# Rocket32_TRASIO.net
KiCad netlist of a schematic drawn in EAGLE
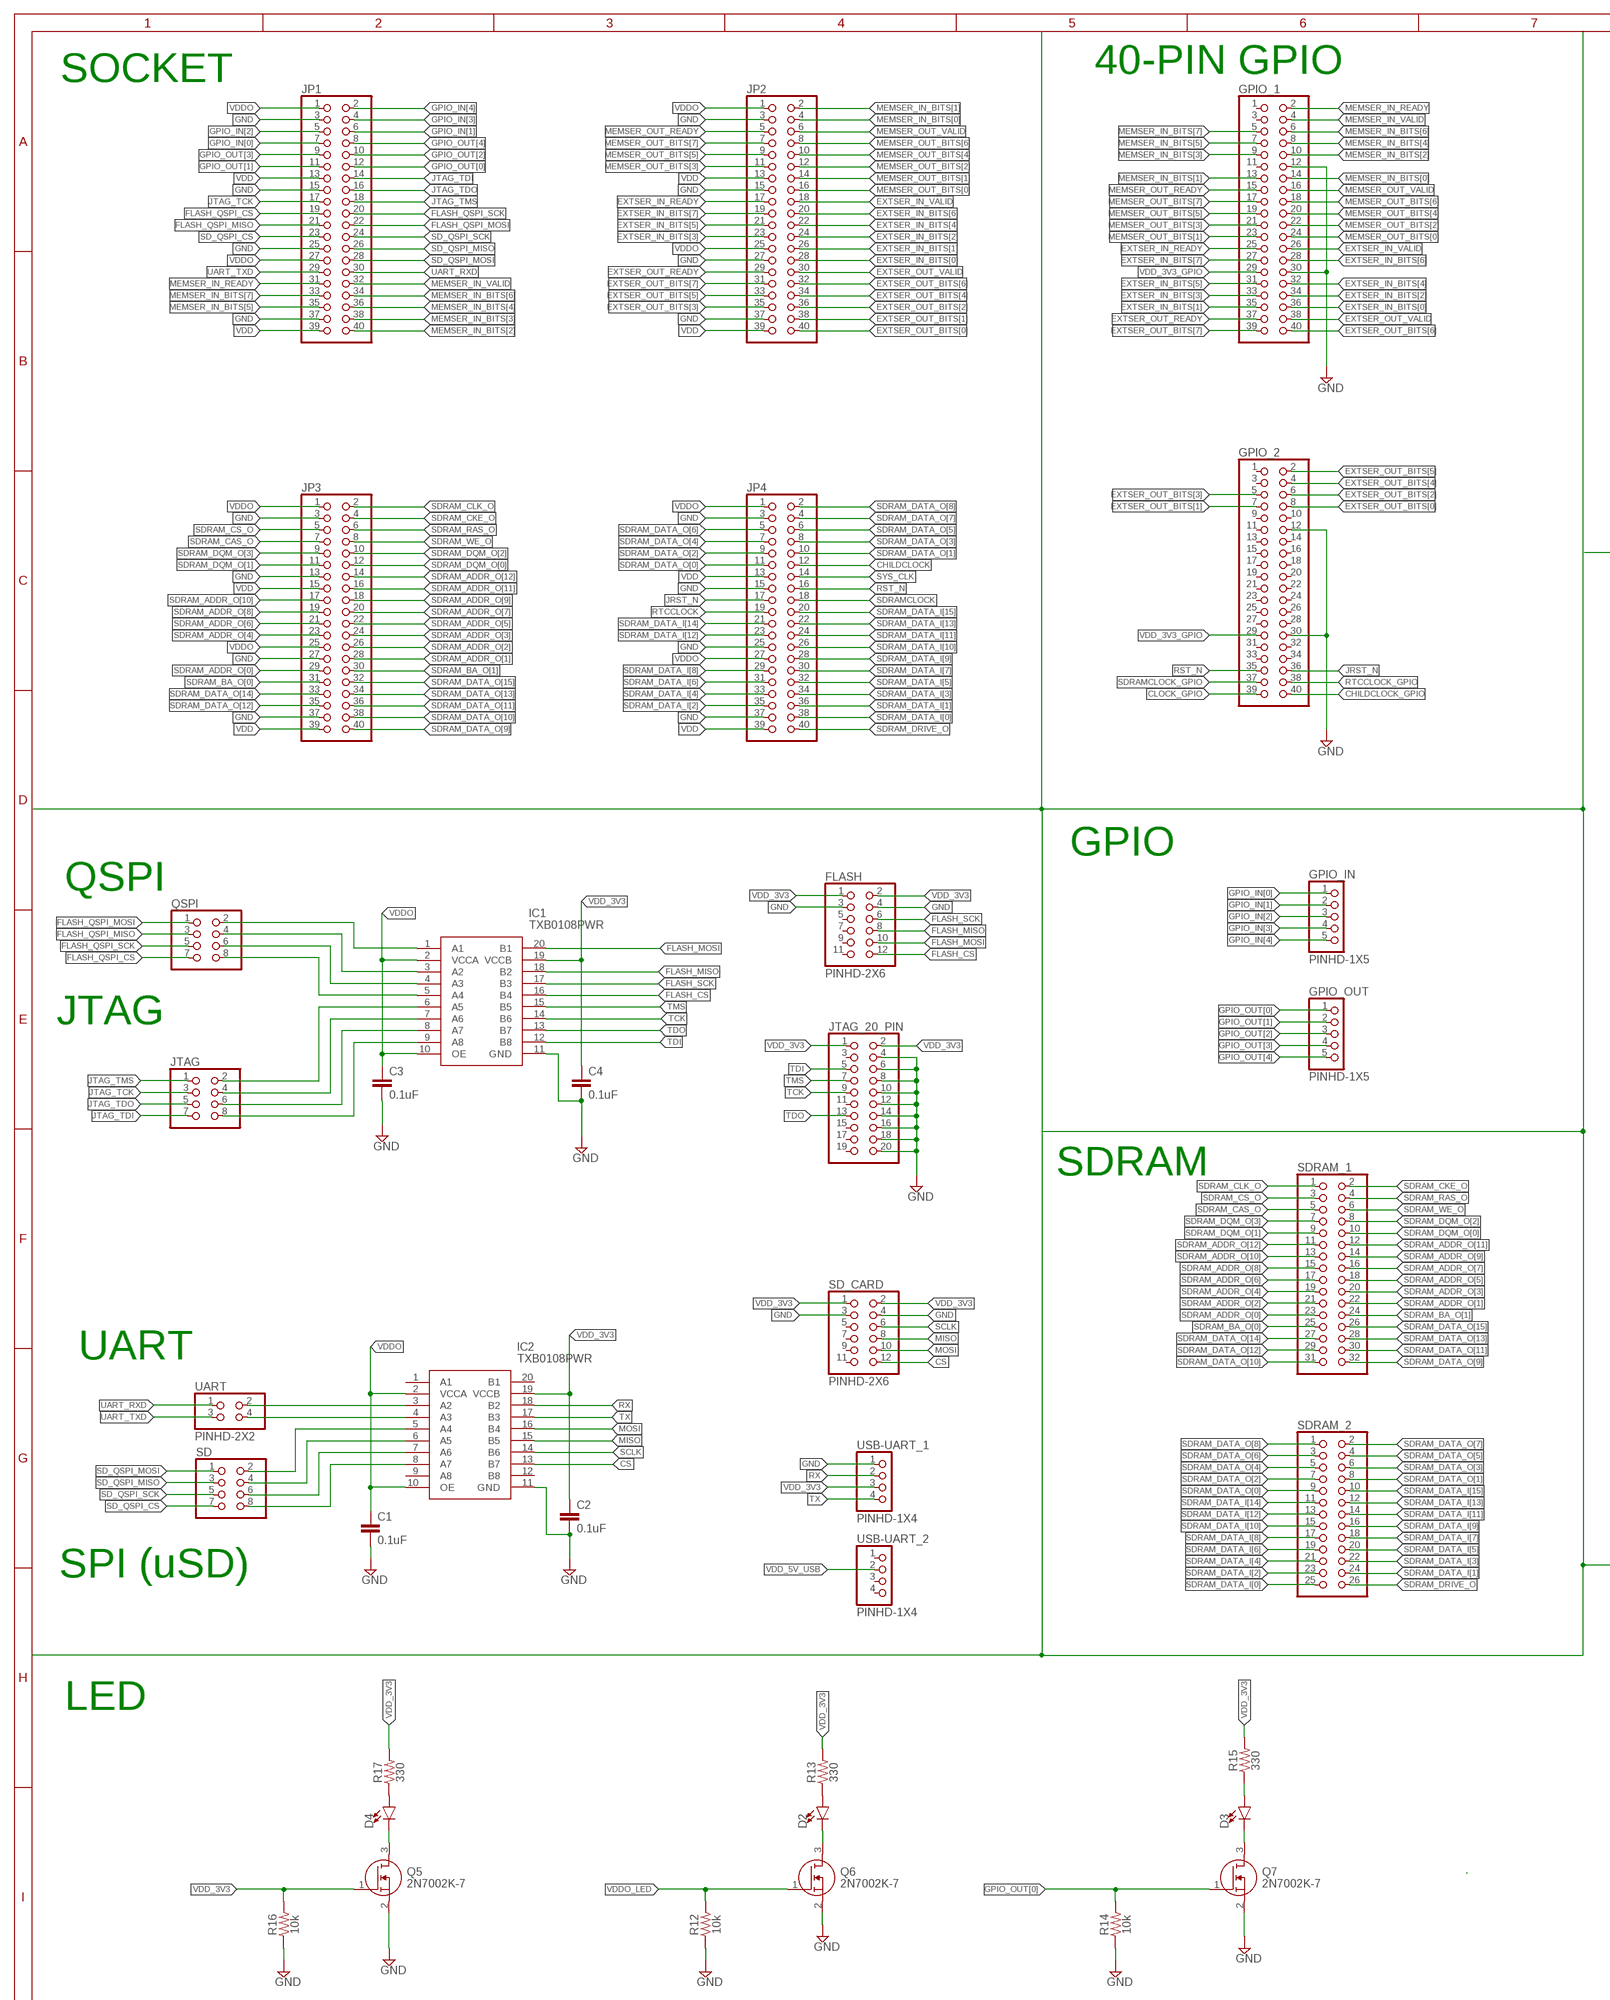
[diagram p0: schematic, sheet 1, part 1 of 2]
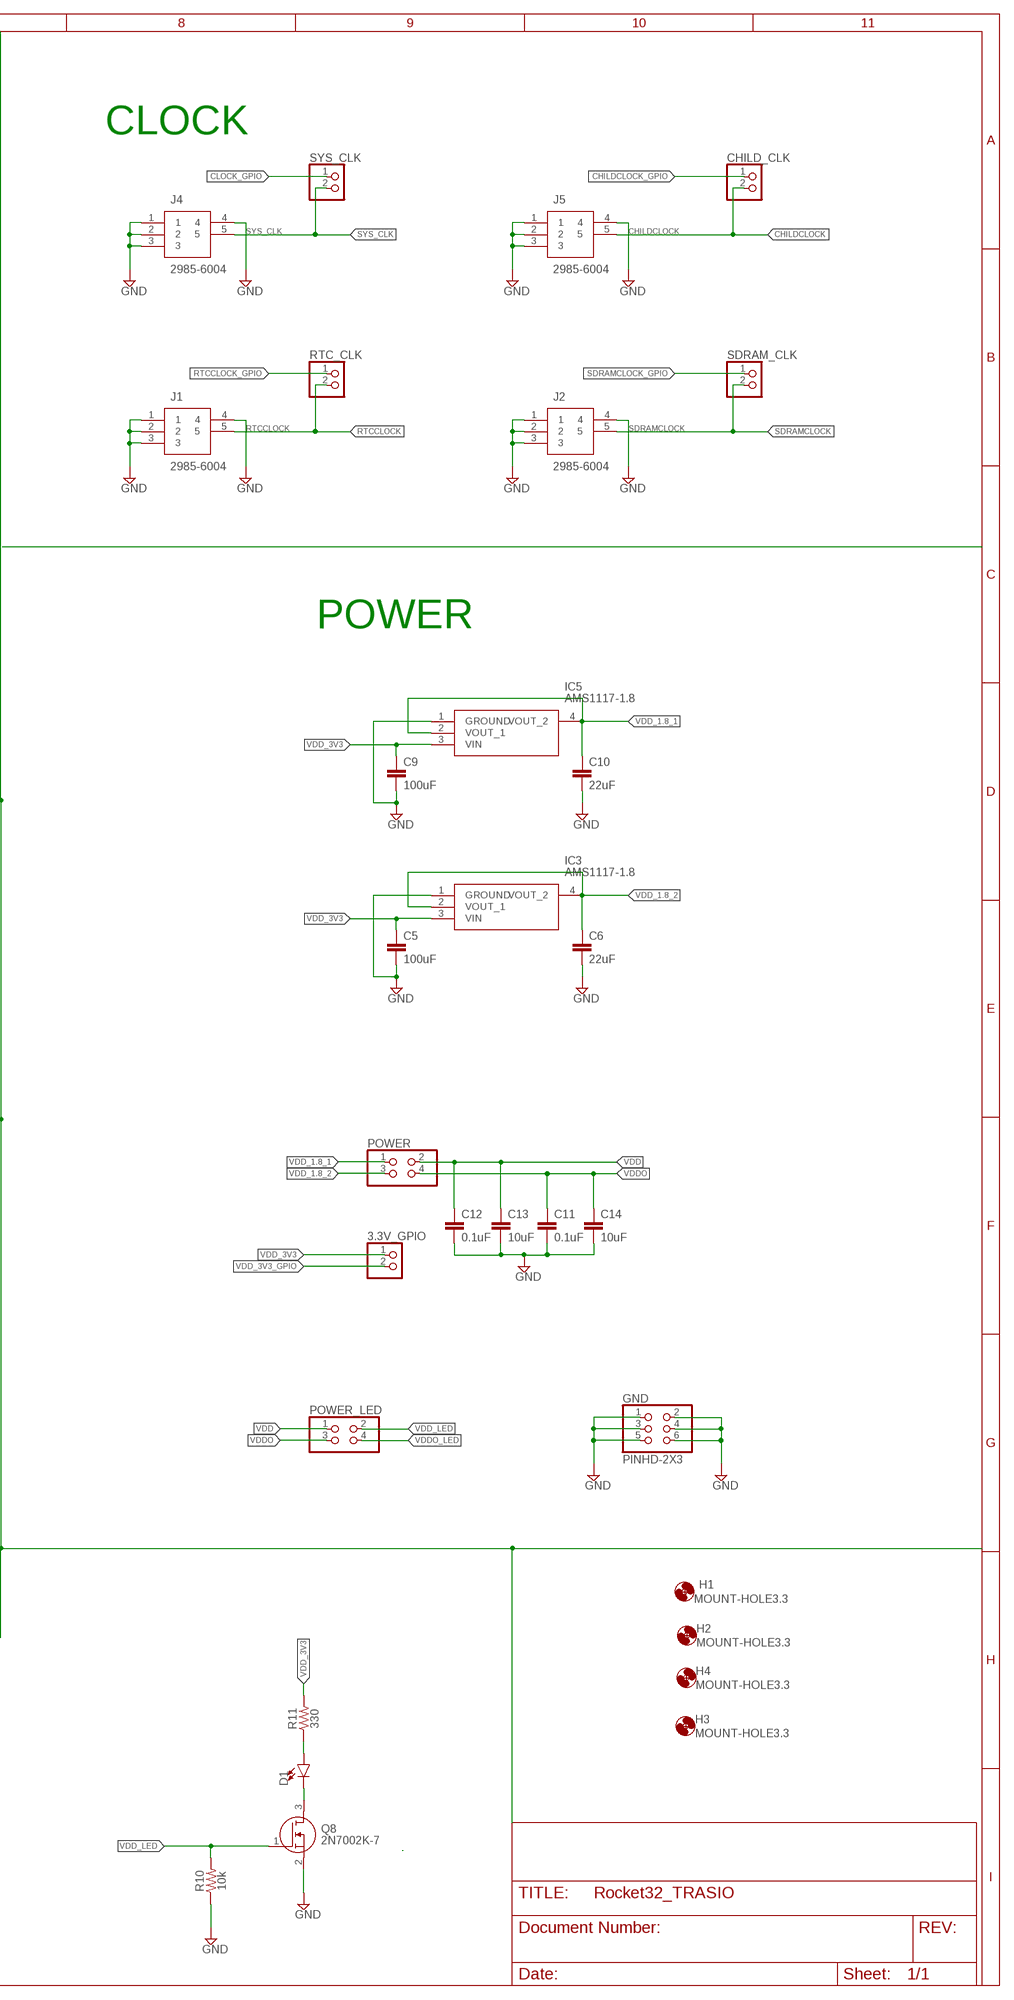
[diagram p1: schematic, sheet 1, part 2 of 2]

(export (version "E")
  (design (tool "Eeschema 10.0.6"))
  (components
    (comp (ref "3.3V_GPIO")
      (value "PINHD-1X2")
      (footprint "eagle-import:1X02")
      (libsource (lib "eagle-import") (part "PINHD-1X2"))
    )
    (comp (ref "C1")
      (value "0.1uF")
      (footprint "eagle-import:1206")
      (libsource (lib "eagle-import") (part "1.0UF-1206-50V-10%"))
    )
    (comp (ref "C2")
      (value "0.1uF")
      (footprint "eagle-import:1206")
      (libsource (lib "eagle-import") (part "1.0UF-1206-50V-10%"))
    )
    (comp (ref "C3")
      (value "0.1uF")
      (footprint "eagle-import:1206")
      (libsource (lib "eagle-import") (part "1.0UF-1206-50V-10%"))
    )
    (comp (ref "C4")
      (value "0.1uF")
      (footprint "eagle-import:1206")
      (libsource (lib "eagle-import") (part "1.0UF-1206-50V-10%"))
    )
    (comp (ref "C5")
      (value "100uF")
      (footprint "eagle-import:1206")
      (libsource (lib "eagle-import") (part "1.0UF-1206-50V-10%"))
    )
    (comp (ref "C6")
      (value "22uF")
      (footprint "eagle-import:1206")
      (libsource (lib "eagle-import") (part "1.0UF-1206-50V-10%"))
    )
    (comp (ref "C9")
      (value "100uF")
      (footprint "eagle-import:1206")
      (libsource (lib "eagle-import") (part "1.0UF-1206-50V-10%"))
    )
    (comp (ref "C10")
      (value "22uF")
      (footprint "eagle-import:1206")
      (libsource (lib "eagle-import") (part "1.0UF-1206-50V-10%"))
    )
    (comp (ref "C11")
      (value "0.1uF")
      (footprint "eagle-import:1206")
      (libsource (lib "eagle-import") (part "1.0UF-1206-50V-10%"))
    )
    (comp (ref "C12")
      (value "0.1uF")
      (footprint "eagle-import:1206")
      (libsource (lib "eagle-import") (part "1.0UF-1206-50V-10%"))
    )
    (comp (ref "C13")
      (value "10uF")
      (footprint "eagle-import:1206")
      (libsource (lib "eagle-import") (part "1.0UF-1206-50V-10%"))
    )
    (comp (ref "C14")
      (value "10uF")
      (footprint "eagle-import:1206")
      (libsource (lib "eagle-import") (part "1.0UF-1206-50V-10%"))
    )
    (comp (ref "CHILD_CLK")
      (value "PINHD-1X2")
      (footprint "eagle-import:1X02")
      (libsource (lib "eagle-import") (part "PINHD-1X2"))
    )
    (comp (ref "D1")
      (value "LED1206")
      (footprint "eagle-import:LED-1206")
      (libsource (lib "eagle-import") (part "LED1206"))
    )
    (comp (ref "D2")
      (value "LED1206")
      (footprint "eagle-import:LED-1206")
      (libsource (lib "eagle-import") (part "LED1206"))
    )
    (comp (ref "D3")
      (value "LED1206")
      (footprint "eagle-import:LED-1206")
      (libsource (lib "eagle-import") (part "LED1206"))
    )
    (comp (ref "D4")
      (value "LED1206")
      (footprint "eagle-import:LED-1206")
      (libsource (lib "eagle-import") (part "LED1206"))
    )
    (comp (ref "FLASH")
      (value "PINHD-2X6")
      (footprint "eagle-import:2X06")
      (libsource (lib "eagle-import") (part "PINHD-2X6"))
    )
    (comp (ref "GND")
      (value "PINHD-2X3")
      (footprint "eagle-import:2X03")
      (libsource (lib "eagle-import") (part "PINHD-2X3"))
    )
    (comp (ref "GPIO_1")
      (value "PINHD-2X20")
      (footprint "eagle-import:2X20")
      (libsource (lib "eagle-import") (part "PINHD-2X20"))
    )
    (comp (ref "GPIO_2")
      (value "PINHD-2X20")
      (footprint "eagle-import:2X20")
      (libsource (lib "eagle-import") (part "PINHD-2X20"))
    )
    (comp (ref "GPIO_IN")
      (value "PINHD-1X5")
      (footprint "eagle-import:1X05")
      (libsource (lib "eagle-import") (part "PINHD-1X5"))
    )
    (comp (ref "GPIO_OUT")
      (value "PINHD-1X5")
      (footprint "eagle-import:1X05")
      (libsource (lib "eagle-import") (part "PINHD-1X5"))
    )
    (comp (ref "H1")
      (value "MOUNT-HOLE3.3")
      (footprint "eagle-import:3,3")
      (libsource (lib "eagle-import") (part "MOUNT-HOLE3.3"))
    )
    (comp (ref "H2")
      (value "MOUNT-HOLE3.3")
      (footprint "eagle-import:3,3")
      (libsource (lib "eagle-import") (part "MOUNT-HOLE3.3"))
    )
    (comp (ref "H3")
      (value "MOUNT-HOLE3.3")
      (footprint "eagle-import:3,3")
      (libsource (lib "eagle-import") (part "MOUNT-HOLE3.3"))
    )
    (comp (ref "H4")
      (value "MOUNT-HOLE3.3")
      (footprint "eagle-import:3,3")
      (libsource (lib "eagle-import") (part "MOUNT-HOLE3.3"))
    )
    (comp (ref "IC1")
      (value "TXB0108PWR")
      (footprint "eagle-import:SOP65P640X120-20N")
      (fields (field (name "MOUSER_PART_NUMBER") "595-TXB0108PWR"))
      (libsource (lib "eagle-import") (part "TXB0108PWR"))
    )
    (comp (ref "IC2")
      (value "TXB0108PWR")
      (footprint "eagle-import:SOP65P640X120-20N")
      (fields (field (name "MOUSER_PART_NUMBER") "595-TXB0108PWR"))
      (libsource (lib "eagle-import") (part "TXB0108PWR"))
    )
    (comp (ref "IC3")
      (value "AMS1117-1.8")
      (footprint "eagle-import:SOT229P700X180-4N")
      (fields (field (name "MANUFACTURER_PART_NUMBER") "AMS1117"))
      (libsource (lib "eagle-import") (part "AMS1117"))
    )
    (comp (ref "IC5")
      (value "AMS1117-1.8")
      (footprint "eagle-import:SOT229P700X180-4N")
      (fields (field (name "MANUFACTURER_PART_NUMBER") "AMS1117"))
      (libsource (lib "eagle-import") (part "AMS1117"))
    )
    (comp (ref "J1")
      (value "2985-6004")
      (footprint "eagle-import:29856004")
      (fields (field (name "MOUSER_PART_NUMBER") "523-2985-6004"))
      (libsource (lib "eagle-import") (part "2985-6004"))
    )
    (comp (ref "J2")
      (value "2985-6004")
      (footprint "eagle-import:29856004")
      (fields (field (name "MOUSER_PART_NUMBER") "523-2985-6004"))
      (libsource (lib "eagle-import") (part "2985-6004"))
    )
    (comp (ref "J4")
      (value "2985-6004")
      (footprint "eagle-import:29856004")
      (fields (field (name "MOUSER_PART_NUMBER") "523-2985-6004"))
      (libsource (lib "eagle-import") (part "2985-6004"))
    )
    (comp (ref "J5")
      (value "2985-6004")
      (footprint "eagle-import:29856004")
      (fields (field (name "MOUSER_PART_NUMBER") "523-2985-6004"))
      (libsource (lib "eagle-import") (part "2985-6004"))
    )
    (comp (ref "JP1")
      (value "PINHD-2X20")
      (footprint "eagle-import:2X20")
      (libsource (lib "eagle-import") (part "PINHD-2X20"))
    )
    (comp (ref "JP2")
      (value "PINHD-2X20")
      (footprint "eagle-import:2X20")
      (libsource (lib "eagle-import") (part "PINHD-2X20"))
    )
    (comp (ref "JP3")
      (value "PINHD-2X20")
      (footprint "eagle-import:2X20")
      (libsource (lib "eagle-import") (part "PINHD-2X20"))
    )
    (comp (ref "JP4")
      (value "PINHD-2X20")
      (footprint "eagle-import:2X20")
      (libsource (lib "eagle-import") (part "PINHD-2X20"))
    )
    (comp (ref "JTAG")
      (value "PINHD-2X4")
      (footprint "eagle-import:2X04")
      (libsource (lib "eagle-import") (part "PINHD-2X4"))
    )
    (comp (ref "JTAG_20_PIN")
      (value "PINHD-2X10")
      (footprint "eagle-import:2X10")
      (libsource (lib "eagle-import") (part "PINHD-2X10"))
    )
    (comp (ref "POWER")
      (value "PINHD-2X2")
      (footprint "eagle-import:2X02")
      (libsource (lib "eagle-import") (part "pinhead_325_PINHD-2X2"))
    )
    (comp (ref "POWER_LED")
      (value "PINHD-2X2")
      (footprint "eagle-import:2X02")
      (libsource (lib "eagle-import") (part "pinhead_325_PINHD-2X2"))
    )
    (comp (ref "Q5")
      (value "2N7002K-7")
      (footprint "eagle-import:SOT96P240X100-3N")
      (fields (field (name "MOUSER_PART_NUMBER") "621-2N7002K-7"))
      (libsource (lib "eagle-import") (part "2N7002K-7"))
    )
    (comp (ref "Q6")
      (value "2N7002K-7")
      (footprint "eagle-import:SOT96P240X100-3N")
      (fields (field (name "MOUSER_PART_NUMBER") "621-2N7002K-7"))
      (libsource (lib "eagle-import") (part "2N7002K-7"))
    )
    (comp (ref "Q7")
      (value "2N7002K-7")
      (footprint "eagle-import:SOT96P240X100-3N")
      (fields (field (name "MOUSER_PART_NUMBER") "621-2N7002K-7"))
      (libsource (lib "eagle-import") (part "2N7002K-7"))
    )
    (comp (ref "Q8")
      (value "2N7002K-7")
      (footprint "eagle-import:SOT96P240X100-3N")
      (fields (field (name "MOUSER_PART_NUMBER") "621-2N7002K-7"))
      (libsource (lib "eagle-import") (part "2N7002K-7"))
    )
    (comp (ref "QSPI")
      (value "PINHD-2X4")
      (footprint "eagle-import:2X04")
      (libsource (lib "eagle-import") (part "PINHD-2X4"))
    )
    (comp (ref "R10")
      (value "10k")
      (footprint "eagle-import:1206")
      (libsource (lib "eagle-import") (part "RESISTOR1206"))
    )
    (comp (ref "R11")
      (value "330")
      (footprint "eagle-import:1206")
      (libsource (lib "eagle-import") (part "RESISTOR1206"))
    )
    (comp (ref "R12")
      (value "10k")
      (footprint "eagle-import:1206")
      (libsource (lib "eagle-import") (part "RESISTOR1206"))
    )
    (comp (ref "R13")
      (value "330")
      (footprint "eagle-import:1206")
      (libsource (lib "eagle-import") (part "RESISTOR1206"))
    )
    (comp (ref "R14")
      (value "10k")
      (footprint "eagle-import:1206")
      (libsource (lib "eagle-import") (part "RESISTOR1206"))
    )
    (comp (ref "R15")
      (value "330")
      (footprint "eagle-import:1206")
      (libsource (lib "eagle-import") (part "RESISTOR1206"))
    )
    (comp (ref "R16")
      (value "10k")
      (footprint "eagle-import:1206")
      (libsource (lib "eagle-import") (part "RESISTOR1206"))
    )
    (comp (ref "R17")
      (value "330")
      (footprint "eagle-import:1206")
      (libsource (lib "eagle-import") (part "RESISTOR1206"))
    )
    (comp (ref "RTC_CLK")
      (value "PINHD-1X2")
      (footprint "eagle-import:1X02")
      (libsource (lib "eagle-import") (part "PINHD-1X2"))
    )
    (comp (ref "SD")
      (value "PINHD-2X4")
      (footprint "eagle-import:2X04")
      (libsource (lib "eagle-import") (part "PINHD-2X4"))
    )
    (comp (ref "SDRAM_1")
      (value "PINHD-2X16")
      (footprint "eagle-import:2X16")
      (libsource (lib "eagle-import") (part "PINHD-2X16"))
    )
    (comp (ref "SDRAM_2")
      (value "PINHD-2X13")
      (footprint "eagle-import:2X13")
      (libsource (lib "eagle-import") (part "PINHD-2X13"))
    )
    (comp (ref "SDRAM_CLK")
      (value "PINHD-1X2")
      (footprint "eagle-import:1X02")
      (libsource (lib "eagle-import") (part "PINHD-1X2"))
    )
    (comp (ref "SD_CARD")
      (value "PINHD-2X6")
      (footprint "eagle-import:2X06")
      (libsource (lib "eagle-import") (part "PINHD-2X6"))
    )
    (comp (ref "SYS_CLK")
      (value "PINHD-1X2")
      (footprint "eagle-import:1X02")
      (libsource (lib "eagle-import") (part "PINHD-1X2"))
    )
    (comp (ref "UART")
      (value "PINHD-2X2")
      (footprint "eagle-import:2X02")
      (libsource (lib "eagle-import") (part "PINHD-2X2"))
    )
    (comp (ref "USB-UART_1")
      (value "PINHD-1X4")
      (footprint "eagle-import:1X04")
      (libsource (lib "eagle-import") (part "PINHD-1X4"))
    )
    (comp (ref "USB-UART_2")
      (value "PINHD-1X4")
      (footprint "eagle-import:1X04")
      (libsource (lib "eagle-import") (part "PINHD-1X4"))
    )
  )
  (nets
    (net (code "1") (name "CHILDCLOCK") (class "Default")
      (node (ref "CHILD_CLK") (pin "2") (pinfunction "2_2") (pintype "passive"))
      (node (ref "J5") (pin "5") (pinfunction "5_5") (pintype "bidirectional"))
      (node (ref "JP4") (pin "12") (pinfunction "12_12") (pintype "passive"))
    )
    (net (code "2") (name "CHILDCLOCK_GPIO") (class "Default")
      (node (ref "CHILD_CLK") (pin "1") (pinfunction "1_1") (pintype "passive"))
      (node (ref "GPIO_2") (pin "40") (pinfunction "40_40") (pintype "passive"))
    )
    (net (code "3") (name "CLOCK_GPIO") (class "Default")
      (node (ref "GPIO_2") (pin "39") (pinfunction "39_39") (pintype "passive"))
      (node (ref "SYS_CLK") (pin "1") (pinfunction "1_1") (pintype "passive"))
    )
    (net (code "4") (name "CS") (class "Default")
      (node (ref "IC2") (pin "13") (pinfunction "B7_13") (pintype "bidirectional"))
      (node (ref "SD_CARD") (pin "12") (pinfunction "12_12") (pintype "passive"))
    )
    (net (code "5") (name "EXTSER_IN_BITS[0]") (class "Default")
      (node (ref "GPIO_1") (pin "36") (pinfunction "36_36") (pintype "passive"))
      (node (ref "JP2") (pin "28") (pinfunction "28_28") (pintype "passive"))
    )
    (net (code "6") (name "EXTSER_IN_BITS[1]") (class "Default")
      (node (ref "GPIO_1") (pin "35") (pinfunction "35_35") (pintype "passive"))
      (node (ref "JP2") (pin "26") (pinfunction "26_26") (pintype "passive"))
    )
    (net (code "7") (name "EXTSER_IN_BITS[2]") (class "Default")
      (node (ref "GPIO_1") (pin "34") (pinfunction "34_34") (pintype "passive"))
      (node (ref "JP2") (pin "24") (pinfunction "24_24") (pintype "passive"))
    )
    (net (code "8") (name "EXTSER_IN_BITS[3]") (class "Default")
      (node (ref "GPIO_1") (pin "33") (pinfunction "33_33") (pintype "passive"))
      (node (ref "JP2") (pin "23") (pinfunction "23_23") (pintype "passive"))
    )
    (net (code "9") (name "EXTSER_IN_BITS[4]") (class "Default")
      (node (ref "GPIO_1") (pin "32") (pinfunction "32_32") (pintype "passive"))
      (node (ref "JP2") (pin "22") (pinfunction "22_22") (pintype "passive"))
    )
    (net (code "10") (name "EXTSER_IN_BITS[5]") (class "Default")
      (node (ref "GPIO_1") (pin "31") (pinfunction "31_31") (pintype "passive"))
      (node (ref "JP2") (pin "21") (pinfunction "21_21") (pintype "passive"))
    )
    (net (code "11") (name "EXTSER_IN_BITS[6]") (class "Default")
      (node (ref "GPIO_1") (pin "28") (pinfunction "28_28") (pintype "passive"))
      (node (ref "JP2") (pin "20") (pinfunction "20_20") (pintype "passive"))
    )
    (net (code "12") (name "EXTSER_IN_BITS[7]") (class "Default")
      (node (ref "GPIO_1") (pin "27") (pinfunction "27_27") (pintype "passive"))
      (node (ref "JP2") (pin "19") (pinfunction "19_19") (pintype "passive"))
    )
    (net (code "13") (name "EXTSER_IN_READY") (class "Default")
      (node (ref "GPIO_1") (pin "25") (pinfunction "25_25") (pintype "passive"))
      (node (ref "JP2") (pin "17") (pinfunction "17_17") (pintype "passive"))
    )
    (net (code "14") (name "EXTSER_IN_VALID") (class "Default")
      (node (ref "GPIO_1") (pin "26") (pinfunction "26_26") (pintype "passive"))
      (node (ref "JP2") (pin "18") (pinfunction "18_18") (pintype "passive"))
    )
    (net (code "15") (name "EXTSER_OUT_BITS[0]") (class "Default")
      (node (ref "GPIO_2") (pin "8") (pinfunction "8_8") (pintype "passive"))
      (node (ref "JP2") (pin "40") (pinfunction "40_40") (pintype "passive"))
    )
    (net (code "16") (name "EXTSER_OUT_BITS[1]") (class "Default")
      (node (ref "GPIO_2") (pin "7") (pinfunction "7_7") (pintype "passive"))
      (node (ref "JP2") (pin "38") (pinfunction "38_38") (pintype "passive"))
    )
    (net (code "17") (name "EXTSER_OUT_BITS[2]") (class "Default")
      (node (ref "GPIO_2") (pin "6") (pinfunction "6_6") (pintype "passive"))
      (node (ref "JP2") (pin "36") (pinfunction "36_36") (pintype "passive"))
    )
    (net (code "18") (name "EXTSER_OUT_BITS[3]") (class "Default")
      (node (ref "GPIO_2") (pin "5") (pinfunction "5_5") (pintype "passive"))
      (node (ref "JP2") (pin "35") (pinfunction "35_35") (pintype "passive"))
    )
    (net (code "19") (name "EXTSER_OUT_BITS[4]") (class "Default")
      (node (ref "GPIO_2") (pin "4") (pinfunction "4_4") (pintype "passive"))
      (node (ref "JP2") (pin "34") (pinfunction "34_34") (pintype "passive"))
    )
    (net (code "20") (name "EXTSER_OUT_BITS[5]") (class "Default")
      (node (ref "GPIO_2") (pin "2") (pinfunction "2_2") (pintype "passive"))
      (node (ref "JP2") (pin "33") (pinfunction "33_33") (pintype "passive"))
    )
    (net (code "21") (name "EXTSER_OUT_BITS[6]") (class "Default")
      (node (ref "GPIO_1") (pin "40") (pinfunction "40_40") (pintype "passive"))
      (node (ref "JP2") (pin "32") (pinfunction "32_32") (pintype "passive"))
    )
    (net (code "22") (name "EXTSER_OUT_BITS[7]") (class "Default")
      (node (ref "GPIO_1") (pin "39") (pinfunction "39_39") (pintype "passive"))
      (node (ref "JP2") (pin "31") (pinfunction "31_31") (pintype "passive"))
    )
    (net (code "23") (name "EXTSER_OUT_READY") (class "Default")
      (node (ref "GPIO_1") (pin "37") (pinfunction "37_37") (pintype "passive"))
      (node (ref "JP2") (pin "29") (pinfunction "29_29") (pintype "passive"))
    )
    (net (code "24") (name "EXTSER_OUT_VALID") (class "Default")
      (node (ref "GPIO_1") (pin "38") (pinfunction "38_38") (pintype "passive"))
      (node (ref "JP2") (pin "30") (pinfunction "30_30") (pintype "passive"))
    )
    (net (code "25") (name "FLASH_CS") (class "Default")
      (node (ref "FLASH") (pin "12") (pinfunction "12_12") (pintype "passive"))
      (node (ref "IC1") (pin "16") (pinfunction "B4_16") (pintype "bidirectional"))
    )
    (net (code "26") (name "FLASH_MISO") (class "Default")
      (node (ref "FLASH") (pin "8") (pinfunction "8_8") (pintype "passive"))
      (node (ref "IC1") (pin "18") (pinfunction "B2_18") (pintype "bidirectional"))
    )
    (net (code "27") (name "FLASH_MOSI") (class "Default")
      (node (ref "FLASH") (pin "10") (pinfunction "10_10") (pintype "passive"))
      (node (ref "IC1") (pin "20") (pinfunction "B1_20") (pintype "bidirectional"))
    )
    (net (code "28") (name "FLASH_QSPI_CS") (class "Default")
      (node (ref "JP1") (pin "19") (pinfunction "19_19") (pintype "passive"))
      (node (ref "QSPI") (pin "7") (pinfunction "7_7") (pintype "passive"))
    )
    (net (code "29") (name "FLASH_QSPI_MISO") (class "Default")
      (node (ref "JP1") (pin "21") (pinfunction "21_21") (pintype "passive"))
      (node (ref "QSPI") (pin "3") (pinfunction "3_3") (pintype "passive"))
    )
    (net (code "30") (name "FLASH_QSPI_MOSI") (class "Default")
      (node (ref "JP1") (pin "22") (pinfunction "22_22") (pintype "passive"))
      (node (ref "QSPI") (pin "1") (pinfunction "1_1") (pintype "passive"))
    )
    (net (code "31") (name "FLASH_QSPI_SCK") (class "Default")
      (node (ref "JP1") (pin "20") (pinfunction "20_20") (pintype "passive"))
      (node (ref "QSPI") (pin "5") (pinfunction "5_5") (pintype "passive"))
    )
    (net (code "32") (name "FLASH_SCK") (class "Default")
      (node (ref "FLASH") (pin "6") (pinfunction "6_6") (pintype "passive"))
      (node (ref "IC1") (pin "17") (pinfunction "B3_17") (pintype "bidirectional"))
    )
    (net (code "33") (name "GND") (class "Default")
      (node (ref "C1") (pin "2") (pinfunction "2_2") (pintype "passive"))
      (node (ref "C10") (pin "2") (pinfunction "2_2") (pintype "passive"))
      (node (ref "C11") (pin "2") (pinfunction "2_2") (pintype "passive"))
      (node (ref "C12") (pin "2") (pinfunction "2_2") (pintype "passive"))
      (node (ref "C13") (pin "2") (pinfunction "2_2") (pintype "passive"))
      (node (ref "C14") (pin "2") (pinfunction "2_2") (pintype "passive"))
      (node (ref "C2") (pin "2") (pinfunction "2_2") (pintype "passive"))
      (node (ref "C3") (pin "2") (pinfunction "2_2") (pintype "passive"))
      (node (ref "C4") (pin "2") (pinfunction "2_2") (pintype "passive"))
      (node (ref "C5") (pin "2") (pinfunction "2_2") (pintype "passive"))
      (node (ref "C6") (pin "2") (pinfunction "2_2") (pintype "passive"))
      (node (ref "C9") (pin "2") (pinfunction "2_2") (pintype "passive"))
      (node (ref "FLASH") (pin "3") (pinfunction "3_3") (pintype "passive"))
      (node (ref "FLASH") (pin "4") (pinfunction "4_4") (pintype "passive"))
      (node (ref "GND") (pin "1") (pinfunction "1_1") (pintype "passive"))
      (node (ref "GND") (pin "2") (pinfunction "2_2") (pintype "passive"))
      (node (ref "GND") (pin "3") (pinfunction "3_3") (pintype "passive"))
      (node (ref "GND") (pin "4") (pinfunction "4_4") (pintype "passive"))
      (node (ref "GND") (pin "5") (pinfunction "5_5") (pintype "passive"))
      (node (ref "GND") (pin "6") (pinfunction "6_6") (pintype "passive"))
      (node (ref "GPIO_1") (pin "12") (pinfunction "12_12") (pintype "passive"))
      (node (ref "GPIO_1") (pin "30") (pinfunction "30_30") (pintype "passive"))
      (node (ref "GPIO_2") (pin "12") (pinfunction "12_12") (pintype "passive"))
      (node (ref "GPIO_2") (pin "30") (pinfunction "30_30") (pintype "passive"))
      (node (ref "IC1") (pin "11") (pinfunction "GND_11") (pintype "bidirectional"))
      (node (ref "IC2") (pin "11") (pinfunction "GND_11") (pintype "bidirectional"))
      (node (ref "IC3") (pin "1") (pinfunction "GROUND_1") (pintype "bidirectional"))
      (node (ref "IC5") (pin "1") (pinfunction "GROUND_1") (pintype "bidirectional"))
      (node (ref "J1") (pin "1") (pinfunction "1_1") (pintype "bidirectional"))
      (node (ref "J1") (pin "2") (pinfunction "2_2") (pintype "bidirectional"))
      (node (ref "J1") (pin "3") (pinfunction "3_3") (pintype "bidirectional"))
      (node (ref "J1") (pin "4") (pinfunction "4_4") (pintype "bidirectional"))
      (node (ref "J2") (pin "1") (pinfunction "1_1") (pintype "bidirectional"))
      (node (ref "J2") (pin "2") (pinfunction "2_2") (pintype "bidirectional"))
      (node (ref "J2") (pin "3") (pinfunction "3_3") (pintype "bidirectional"))
      (node (ref "J2") (pin "4") (pinfunction "4_4") (pintype "bidirectional"))
      (node (ref "J4") (pin "1") (pinfunction "1_1") (pintype "bidirectional"))
      (node (ref "J4") (pin "2") (pinfunction "2_2") (pintype "bidirectional"))
      (node (ref "J4") (pin "3") (pinfunction "3_3") (pintype "bidirectional"))
      (node (ref "J4") (pin "4") (pinfunction "4_4") (pintype "bidirectional"))
      (node (ref "J5") (pin "1") (pinfunction "1_1") (pintype "bidirectional"))
      (node (ref "J5") (pin "2") (pinfunction "2_2") (pintype "bidirectional"))
      (node (ref "J5") (pin "3") (pinfunction "3_3") (pintype "bidirectional"))
      (node (ref "J5") (pin "4") (pinfunction "4_4") (pintype "bidirectional"))
      (node (ref "JP1") (pin "15") (pinfunction "15_15") (pintype "passive"))
      (node (ref "JP1") (pin "25") (pinfunction "25_25") (pintype "passive"))
      (node (ref "JP1") (pin "3") (pinfunction "3_3") (pintype "passive"))
      (node (ref "JP1") (pin "37") (pinfunction "37_37") (pintype "passive"))
      (node (ref "JP2") (pin "15") (pinfunction "15_15") (pintype "passive"))
      (node (ref "JP2") (pin "27") (pinfunction "27_27") (pintype "passive"))
      (node (ref "JP2") (pin "3") (pinfunction "3_3") (pintype "passive"))
      (node (ref "JP2") (pin "37") (pinfunction "37_37") (pintype "passive"))
      (node (ref "JP3") (pin "13") (pinfunction "13_13") (pintype "passive"))
      (node (ref "JP3") (pin "27") (pinfunction "27_27") (pintype "passive"))
      (node (ref "JP3") (pin "3") (pinfunction "3_3") (pintype "passive"))
      (node (ref "JP3") (pin "37") (pinfunction "37_37") (pintype "passive"))
      (node (ref "JP4") (pin "15") (pinfunction "15_15") (pintype "passive"))
      (node (ref "JP4") (pin "25") (pinfunction "25_25") (pintype "passive"))
      (node (ref "JP4") (pin "3") (pinfunction "3_3") (pintype "passive"))
      (node (ref "JP4") (pin "37") (pinfunction "37_37") (pintype "passive"))
      (node (ref "JTAG_20_PIN") (pin "10") (pinfunction "10_10") (pintype "passive"))
      (node (ref "JTAG_20_PIN") (pin "12") (pinfunction "12_12") (pintype "passive"))
      (node (ref "JTAG_20_PIN") (pin "14") (pinfunction "14_14") (pintype "passive"))
      (node (ref "JTAG_20_PIN") (pin "16") (pinfunction "16_16") (pintype "passive"))
      (node (ref "JTAG_20_PIN") (pin "18") (pinfunction "18_18") (pintype "passive"))
      (node (ref "JTAG_20_PIN") (pin "20") (pinfunction "20_20") (pintype "passive"))
      (node (ref "JTAG_20_PIN") (pin "4") (pinfunction "4_4") (pintype "passive"))
      (node (ref "JTAG_20_PIN") (pin "6") (pinfunction "6_6") (pintype "passive"))
      (node (ref "JTAG_20_PIN") (pin "8") (pinfunction "8_8") (pintype "passive"))
      (node (ref "Q5") (pin "2") (pinfunction "S_2") (pintype "bidirectional"))
      (node (ref "Q6") (pin "2") (pinfunction "S_2") (pintype "bidirectional"))
      (node (ref "Q7") (pin "2") (pinfunction "S_2") (pintype "bidirectional"))
      (node (ref "Q8") (pin "2") (pinfunction "S_2") (pintype "bidirectional"))
      (node (ref "R10") (pin "1") (pinfunction "1_1") (pintype "passive"))
      (node (ref "R12") (pin "1") (pinfunction "1_1") (pintype "passive"))
      (node (ref "R14") (pin "1") (pinfunction "1_1") (pintype "passive"))
      (node (ref "R16") (pin "1") (pinfunction "1_1") (pintype "passive"))
      (node (ref "SD_CARD") (pin "3") (pinfunction "3_3") (pintype "passive"))
      (node (ref "SD_CARD") (pin "4") (pinfunction "4_4") (pintype "passive"))
      (node (ref "USB-UART_1") (pin "1") (pinfunction "1_1") (pintype "passive"))
    )
    (net (code "34") (name "GPIO_IN[0]") (class "Default")
      (node (ref "GPIO_IN") (pin "1") (pinfunction "1_1") (pintype "passive"))
      (node (ref "JP1") (pin "7") (pinfunction "7_7") (pintype "passive"))
    )
    (net (code "35") (name "GPIO_IN[1]") (class "Default")
      (node (ref "GPIO_IN") (pin "2") (pinfunction "2_2") (pintype "passive"))
      (node (ref "JP1") (pin "6") (pinfunction "6_6") (pintype "passive"))
    )
    (net (code "36") (name "GPIO_IN[2]") (class "Default")
      (node (ref "GPIO_IN") (pin "3") (pinfunction "3_3") (pintype "passive"))
      (node (ref "JP1") (pin "5") (pinfunction "5_5") (pintype "passive"))
    )
    (net (code "37") (name "GPIO_IN[3]") (class "Default")
      (node (ref "GPIO_IN") (pin "4") (pinfunction "4_4") (pintype "passive"))
      (node (ref "JP1") (pin "4") (pinfunction "4_4") (pintype "passive"))
    )
    (net (code "38") (name "GPIO_IN[4]") (class "Default")
      (node (ref "GPIO_IN") (pin "5") (pinfunction "5_5") (pintype "passive"))
      (node (ref "JP1") (pin "2") (pinfunction "2_2") (pintype "passive"))
    )
    (net (code "39") (name "GPIO_OUT[0]") (class "Default")
      (node (ref "GPIO_OUT") (pin "1") (pinfunction "1_1") (pintype "passive"))
      (node (ref "JP1") (pin "12") (pinfunction "12_12") (pintype "passive"))
      (node (ref "Q7") (pin "1") (pinfunction "G_1") (pintype "bidirectional"))
      (node (ref "R14") (pin "2") (pinfunction "2_2") (pintype "passive"))
    )
    (net (code "40") (name "GPIO_OUT[1]") (class "Default")
      (node (ref "GPIO_OUT") (pin "2") (pinfunction "2_2") (pintype "passive"))
      (node (ref "JP1") (pin "11") (pinfunction "11_11") (pintype "passive"))
    )
    (net (code "41") (name "GPIO_OUT[2]") (class "Default")
      (node (ref "GPIO_OUT") (pin "3") (pinfunction "3_3") (pintype "passive"))
      (node (ref "JP1") (pin "10") (pinfunction "10_10") (pintype "passive"))
    )
    (net (code "42") (name "GPIO_OUT[3]") (class "Default")
      (node (ref "GPIO_OUT") (pin "4") (pinfunction "4_4") (pintype "passive"))
      (node (ref "JP1") (pin "9") (pinfunction "9_9") (pintype "passive"))
    )
    (net (code "43") (name "GPIO_OUT[4]") (class "Default")
      (node (ref "GPIO_OUT") (pin "5") (pinfunction "5_5") (pintype "passive"))
      (node (ref "JP1") (pin "8") (pinfunction "8_8") (pintype "passive"))
    )
    (net (code "44") (name "JRST_N") (class "Default")
      (node (ref "GPIO_2") (pin "36") (pinfunction "36_36") (pintype "passive"))
      (node (ref "JP4") (pin "17") (pinfunction "17_17") (pintype "passive"))
    )
    (net (code "45") (name "JTAG_TCK") (class "Default")
      (node (ref "JP1") (pin "17") (pinfunction "17_17") (pintype "passive"))
      (node (ref "JTAG") (pin "3") (pinfunction "3_3") (pintype "passive"))
    )
    (net (code "46") (name "JTAG_TDI") (class "Default")
      (node (ref "JP1") (pin "14") (pinfunction "14_14") (pintype "passive"))
      (node (ref "JTAG") (pin "7") (pinfunction "7_7") (pintype "passive"))
    )
    (net (code "47") (name "JTAG_TDO") (class "Default")
      (node (ref "JP1") (pin "16") (pinfunction "16_16") (pintype "passive"))
      (node (ref "JTAG") (pin "5") (pinfunction "5_5") (pintype "passive"))
    )
    (net (code "48") (name "JTAG_TMS") (class "Default")
      (node (ref "JP1") (pin "18") (pinfunction "18_18") (pintype "passive"))
      (node (ref "JTAG") (pin "1") (pinfunction "1_1") (pintype "passive"))
    )
    (net (code "49") (name "MEMSER_IN_BITS[0]") (class "Default")
      (node (ref "GPIO_1") (pin "14") (pinfunction "14_14") (pintype "passive"))
      (node (ref "JP2") (pin "4") (pinfunction "4_4") (pintype "passive"))
    )
    (net (code "50") (name "MEMSER_IN_BITS[1]") (class "Default")
      (node (ref "GPIO_1") (pin "13") (pinfunction "13_13") (pintype "passive"))
      (node (ref "JP2") (pin "2") (pinfunction "2_2") (pintype "passive"))
    )
    (net (code "51") (name "MEMSER_IN_BITS[2]") (class "Default")
      (node (ref "GPIO_1") (pin "10") (pinfunction "10_10") (pintype "passive"))
      (node (ref "JP1") (pin "40") (pinfunction "40_40") (pintype "passive"))
    )
    (net (code "52") (name "MEMSER_IN_BITS[3]") (class "Default")
      (node (ref "GPIO_1") (pin "9") (pinfunction "9_9") (pintype "passive"))
      (node (ref "JP1") (pin "38") (pinfunction "38_38") (pintype "passive"))
    )
    (net (code "53") (name "MEMSER_IN_BITS[4]") (class "Default")
      (node (ref "GPIO_1") (pin "8") (pinfunction "8_8") (pintype "passive"))
      (node (ref "JP1") (pin "36") (pinfunction "36_36") (pintype "passive"))
    )
    (net (code "54") (name "MEMSER_IN_BITS[5]") (class "Default")
      (node (ref "GPIO_1") (pin "7") (pinfunction "7_7") (pintype "passive"))
      (node (ref "JP1") (pin "35") (pinfunction "35_35") (pintype "passive"))
    )
    (net (code "55") (name "MEMSER_IN_BITS[6]") (class "Default")
      (node (ref "GPIO_1") (pin "6") (pinfunction "6_6") (pintype "passive"))
      (node (ref "JP1") (pin "34") (pinfunction "34_34") (pintype "passive"))
    )
    (net (code "56") (name "MEMSER_IN_BITS[7]") (class "Default")
      (node (ref "GPIO_1") (pin "5") (pinfunction "5_5") (pintype "passive"))
      (node (ref "JP1") (pin "33") (pinfunction "33_33") (pintype "passive"))
    )
    (net (code "57") (name "MEMSER_IN_READY") (class "Default")
      (node (ref "GPIO_1") (pin "2") (pinfunction "2_2") (pintype "passive"))
      (node (ref "JP1") (pin "31") (pinfunction "31_31") (pintype "passive"))
    )
    (net (code "58") (name "MEMSER_IN_VALID") (class "Default")
      (node (ref "GPIO_1") (pin "4") (pinfunction "4_4") (pintype "passive"))
      (node (ref "JP1") (pin "32") (pinfunction "32_32") (pintype "passive"))
    )
    (net (code "59") (name "MEMSER_OUT_BITS[0]") (class "Default")
      (node (ref "GPIO_1") (pin "24") (pinfunction "24_24") (pintype "passive"))
      (node (ref "JP2") (pin "16") (pinfunction "16_16") (pintype "passive"))
    )
    (net (code "60") (name "MEMSER_OUT_BITS[1]") (class "Default")
      (node (ref "GPIO_1") (pin "23") (pinfunction "23_23") (pintype "passive"))
      (node (ref "JP2") (pin "14") (pinfunction "14_14") (pintype "passive"))
    )
    (net (code "61") (name "MEMSER_OUT_BITS[2]") (class "Default")
      (node (ref "GPIO_1") (pin "22") (pinfunction "22_22") (pintype "passive"))
      (node (ref "JP2") (pin "12") (pinfunction "12_12") (pintype "passive"))
    )
    (net (code "62") (name "MEMSER_OUT_BITS[3]") (class "Default")
      (node (ref "GPIO_1") (pin "21") (pinfunction "21_21") (pintype "passive"))
      (node (ref "JP2") (pin "11") (pinfunction "11_11") (pintype "passive"))
    )
    (net (code "63") (name "MEMSER_OUT_BITS[4]") (class "Default")
      (node (ref "GPIO_1") (pin "20") (pinfunction "20_20") (pintype "passive"))
      (node (ref "JP2") (pin "10") (pinfunction "10_10") (pintype "passive"))
    )
    (net (code "64") (name "MEMSER_OUT_BITS[5]") (class "Default")
      (node (ref "GPIO_1") (pin "19") (pinfunction "19_19") (pintype "passive"))
      (node (ref "JP2") (pin "9") (pinfunction "9_9") (pintype "passive"))
    )
    (net (code "65") (name "MEMSER_OUT_BITS[6]") (class "Default")
      (node (ref "GPIO_1") (pin "18") (pinfunction "18_18") (pintype "passive"))
      (node (ref "JP2") (pin "8") (pinfunction "8_8") (pintype "passive"))
    )
    (net (code "66") (name "MEMSER_OUT_BITS[7]") (class "Default")
      (node (ref "GPIO_1") (pin "17") (pinfunction "17_17") (pintype "passive"))
      (node (ref "JP2") (pin "7") (pinfunction "7_7") (pintype "passive"))
    )
    (net (code "67") (name "MEMSER_OUT_READY") (class "Default")
      (node (ref "GPIO_1") (pin "15") (pinfunction "15_15") (pintype "passive"))
      (node (ref "JP2") (pin "5") (pinfunction "5_5") (pintype "passive"))
    )
    (net (code "68") (name "MEMSER_OUT_VALID") (class "Default")
      (node (ref "GPIO_1") (pin "16") (pinfunction "16_16") (pintype "passive"))
      (node (ref "JP2") (pin "6") (pinfunction "6_6") (pintype "passive"))
    )
    (net (code "69") (name "MISO") (class "Default")
      (node (ref "IC2") (pin "15") (pinfunction "B5_15") (pintype "bidirectional"))
      (node (ref "SD_CARD") (pin "8") (pinfunction "8_8") (pintype "passive"))
    )
    (net (code "70") (name "MOSI") (class "Default")
      (node (ref "IC2") (pin "16") (pinfunction "B4_16") (pintype "bidirectional"))
      (node (ref "SD_CARD") (pin "10") (pinfunction "10_10") (pintype "passive"))
    )
    (net (code "71") (name "Net-(D1-PadA)") (class "Default")
      (node (ref "D1") (pin "A") (pinfunction "A_A") (pintype "passive"))
      (node (ref "R11") (pin "1") (pinfunction "1_1") (pintype "passive"))
    )
    (net (code "72") (name "Net-(D2-PadA)") (class "Default")
      (node (ref "D2") (pin "A") (pinfunction "A_A") (pintype "passive"))
      (node (ref "R13") (pin "1") (pinfunction "1_1") (pintype "passive"))
    )
    (net (code "73") (name "Net-(D3-PadA)") (class "Default")
      (node (ref "D3") (pin "A") (pinfunction "A_A") (pintype "passive"))
      (node (ref "R15") (pin "1") (pinfunction "1_1") (pintype "passive"))
    )
    (net (code "74") (name "Net-(D4-PadA)") (class "Default")
      (node (ref "D4") (pin "A") (pinfunction "A_A") (pintype "passive"))
      (node (ref "R17") (pin "1") (pinfunction "1_1") (pintype "passive"))
    )
    (net (code "75") (name "Net-(IC1-A1)") (class "Default")
      (node (ref "IC1") (pin "1") (pinfunction "A1_1") (pintype "bidirectional"))
      (node (ref "QSPI") (pin "2") (pinfunction "2_2") (pintype "passive"))
    )
    (net (code "76") (name "Net-(IC1-A2)") (class "Default")
      (node (ref "IC1") (pin "3") (pinfunction "A2_3") (pintype "bidirectional"))
      (node (ref "QSPI") (pin "4") (pinfunction "4_4") (pintype "passive"))
    )
    (net (code "77") (name "Net-(IC1-A3)") (class "Default")
      (node (ref "IC1") (pin "4") (pinfunction "A3_4") (pintype "bidirectional"))
      (node (ref "QSPI") (pin "6") (pinfunction "6_6") (pintype "passive"))
    )
    (net (code "78") (name "Net-(IC1-A4)") (class "Default")
      (node (ref "IC1") (pin "5") (pinfunction "A4_5") (pintype "bidirectional"))
      (node (ref "QSPI") (pin "8") (pinfunction "8_8") (pintype "passive"))
    )
    (net (code "79") (name "Net-(IC1-A5)") (class "Default")
      (node (ref "IC1") (pin "6") (pinfunction "A5_6") (pintype "bidirectional"))
      (node (ref "JTAG") (pin "2") (pinfunction "2_2") (pintype "passive"))
    )
    (net (code "80") (name "Net-(IC1-A6)") (class "Default")
      (node (ref "IC1") (pin "7") (pinfunction "A6_7") (pintype "bidirectional"))
      (node (ref "JTAG") (pin "4") (pinfunction "4_4") (pintype "passive"))
    )
    (net (code "81") (name "Net-(IC1-A7)") (class "Default")
      (node (ref "IC1") (pin "8") (pinfunction "A7_8") (pintype "bidirectional"))
      (node (ref "JTAG") (pin "6") (pinfunction "6_6") (pintype "passive"))
    )
    (net (code "82") (name "Net-(IC1-A8)") (class "Default")
      (node (ref "IC1") (pin "9") (pinfunction "A8_9") (pintype "bidirectional"))
      (node (ref "JTAG") (pin "8") (pinfunction "8_8") (pintype "passive"))
    )
    (net (code "83") (name "Net-(IC2-A2)") (class "Default")
      (node (ref "IC2") (pin "3") (pinfunction "A2_3") (pintype "bidirectional"))
      (node (ref "UART") (pin "2") (pinfunction "2_2") (pintype "passive"))
    )
    (net (code "84") (name "Net-(IC2-A3)") (class "Default")
      (node (ref "IC2") (pin "4") (pinfunction "A3_4") (pintype "bidirectional"))
      (node (ref "UART") (pin "4") (pinfunction "4_4") (pintype "passive"))
    )
    (net (code "85") (name "Net-(IC2-A4)") (class "Default")
      (node (ref "IC2") (pin "5") (pinfunction "A4_5") (pintype "bidirectional"))
      (node (ref "SD") (pin "2") (pinfunction "2_2") (pintype "passive"))
    )
    (net (code "86") (name "Net-(IC2-A5)") (class "Default")
      (node (ref "IC2") (pin "6") (pinfunction "A5_6") (pintype "bidirectional"))
      (node (ref "SD") (pin "4") (pinfunction "4_4") (pintype "passive"))
    )
    (net (code "87") (name "Net-(IC2-A6)") (class "Default")
      (node (ref "IC2") (pin "7") (pinfunction "A6_7") (pintype "bidirectional"))
      (node (ref "SD") (pin "6") (pinfunction "6_6") (pintype "passive"))
    )
    (net (code "88") (name "Net-(IC2-A7)") (class "Default")
      (node (ref "IC2") (pin "8") (pinfunction "A7_8") (pintype "bidirectional"))
      (node (ref "SD") (pin "8") (pinfunction "8_8") (pintype "passive"))
    )
    (net (code "89") (name "Net-(Q5-D)") (class "Default")
      (node (ref "D4") (pin "C") (pinfunction "C_C") (pintype "passive"))
      (node (ref "Q5") (pin "3") (pinfunction "D_3") (pintype "bidirectional"))
    )
    (net (code "90") (name "Net-(Q6-D)") (class "Default")
      (node (ref "D2") (pin "C") (pinfunction "C_C") (pintype "passive"))
      (node (ref "Q6") (pin "3") (pinfunction "D_3") (pintype "bidirectional"))
    )
    (net (code "91") (name "Net-(Q7-D)") (class "Default")
      (node (ref "D3") (pin "C") (pinfunction "C_C") (pintype "passive"))
      (node (ref "Q7") (pin "3") (pinfunction "D_3") (pintype "bidirectional"))
    )
    (net (code "92") (name "Net-(Q8-D)") (class "Default")
      (node (ref "D1") (pin "C") (pinfunction "C_C") (pintype "passive"))
      (node (ref "Q8") (pin "3") (pinfunction "D_3") (pintype "bidirectional"))
    )
    (net (code "93") (name "RST_N") (class "Default")
      (node (ref "GPIO_2") (pin "35") (pinfunction "35_35") (pintype "passive"))
      (node (ref "JP4") (pin "16") (pinfunction "16_16") (pintype "passive"))
    )
    (net (code "94") (name "RTCCLOCK") (class "Default")
      (node (ref "J1") (pin "5") (pinfunction "5_5") (pintype "bidirectional"))
      (node (ref "JP4") (pin "19") (pinfunction "19_19") (pintype "passive"))
      (node (ref "RTC_CLK") (pin "2") (pinfunction "2_2") (pintype "passive"))
    )
    (net (code "95") (name "RTCCLOCK_GPIO") (class "Default")
      (node (ref "GPIO_2") (pin "38") (pinfunction "38_38") (pintype "passive"))
      (node (ref "RTC_CLK") (pin "1") (pinfunction "1_1") (pintype "passive"))
    )
    (net (code "96") (name "RX") (class "Default")
      (node (ref "IC2") (pin "18") (pinfunction "B2_18") (pintype "bidirectional"))
      (node (ref "USB-UART_1") (pin "2") (pinfunction "2_2") (pintype "passive"))
    )
    (net (code "97") (name "SCLK") (class "Default")
      (node (ref "IC2") (pin "14") (pinfunction "B6_14") (pintype "bidirectional"))
      (node (ref "SD_CARD") (pin "6") (pinfunction "6_6") (pintype "passive"))
    )
    (net (code "98") (name "SDRAMCLOCK") (class "Default")
      (node (ref "J2") (pin "5") (pinfunction "5_5") (pintype "bidirectional"))
      (node (ref "JP4") (pin "18") (pinfunction "18_18") (pintype "passive"))
      (node (ref "SDRAM_CLK") (pin "2") (pinfunction "2_2") (pintype "passive"))
    )
    (net (code "99") (name "SDRAMCLOCK_GPIO") (class "Default")
      (node (ref "GPIO_2") (pin "37") (pinfunction "37_37") (pintype "passive"))
      (node (ref "SDRAM_CLK") (pin "1") (pinfunction "1_1") (pintype "passive"))
    )
    (net (code "100") (name "SDRAM_ADDR_O[0]") (class "Default")
      (node (ref "JP3") (pin "29") (pinfunction "29_29") (pintype "passive"))
      (node (ref "SDRAM_1") (pin "23") (pinfunction "23_23") (pintype "passive"))
    )
    (net (code "101") (name "SDRAM_ADDR_O[1]") (class "Default")
      (node (ref "JP3") (pin "28") (pinfunction "28_28") (pintype "passive"))
      (node (ref "SDRAM_1") (pin "22") (pinfunction "22_22") (pintype "passive"))
    )
    (net (code "102") (name "SDRAM_ADDR_O[2]") (class "Default")
      (node (ref "JP3") (pin "26") (pinfunction "26_26") (pintype "passive"))
      (node (ref "SDRAM_1") (pin "21") (pinfunction "21_21") (pintype "passive"))
    )
    (net (code "103") (name "SDRAM_ADDR_O[3]") (class "Default")
      (node (ref "JP3") (pin "24") (pinfunction "24_24") (pintype "passive"))
      (node (ref "SDRAM_1") (pin "20") (pinfunction "20_20") (pintype "passive"))
    )
    (net (code "104") (name "SDRAM_ADDR_O[4]") (class "Default")
      (node (ref "JP3") (pin "23") (pinfunction "23_23") (pintype "passive"))
      (node (ref "SDRAM_1") (pin "19") (pinfunction "19_19") (pintype "passive"))
    )
    (net (code "105") (name "SDRAM_ADDR_O[5]") (class "Default")
      (node (ref "JP3") (pin "22") (pinfunction "22_22") (pintype "passive"))
      (node (ref "SDRAM_1") (pin "18") (pinfunction "18_18") (pintype "passive"))
    )
    (net (code "106") (name "SDRAM_ADDR_O[6]") (class "Default")
      (node (ref "JP3") (pin "21") (pinfunction "21_21") (pintype "passive"))
      (node (ref "SDRAM_1") (pin "17") (pinfunction "17_17") (pintype "passive"))
    )
    (net (code "107") (name "SDRAM_ADDR_O[7]") (class "Default")
      (node (ref "JP3") (pin "20") (pinfunction "20_20") (pintype "passive"))
      (node (ref "SDRAM_1") (pin "16") (pinfunction "16_16") (pintype "passive"))
    )
    (net (code "108") (name "SDRAM_ADDR_O[8]") (class "Default")
      (node (ref "JP3") (pin "19") (pinfunction "19_19") (pintype "passive"))
      (node (ref "SDRAM_1") (pin "15") (pinfunction "15_15") (pintype "passive"))
    )
    (net (code "109") (name "SDRAM_ADDR_O[9]") (class "Default")
      (node (ref "JP3") (pin "18") (pinfunction "18_18") (pintype "passive"))
      (node (ref "SDRAM_1") (pin "14") (pinfunction "14_14") (pintype "passive"))
    )
    (net (code "110") (name "SDRAM_ADDR_O[10]") (class "Default")
      (node (ref "JP3") (pin "17") (pinfunction "17_17") (pintype "passive"))
      (node (ref "SDRAM_1") (pin "13") (pinfunction "13_13") (pintype "passive"))
    )
    (net (code "111") (name "SDRAM_ADDR_O[11]") (class "Default")
      (node (ref "JP3") (pin "16") (pinfunction "16_16") (pintype "passive"))
      (node (ref "SDRAM_1") (pin "12") (pinfunction "12_12") (pintype "passive"))
    )
    (net (code "112") (name "SDRAM_ADDR_O[12]") (class "Default")
      (node (ref "JP3") (pin "14") (pinfunction "14_14") (pintype "passive"))
      (node (ref "SDRAM_1") (pin "11") (pinfunction "11_11") (pintype "passive"))
    )
    (net (code "113") (name "SDRAM_BA_O[0]") (class "Default")
      (node (ref "JP3") (pin "31") (pinfunction "31_31") (pintype "passive"))
      (node (ref "SDRAM_1") (pin "25") (pinfunction "25_25") (pintype "passive"))
    )
    (net (code "114") (name "SDRAM_BA_O[1]") (class "Default")
      (node (ref "JP3") (pin "30") (pinfunction "30_30") (pintype "passive"))
      (node (ref "SDRAM_1") (pin "24") (pinfunction "24_24") (pintype "passive"))
    )
    (net (code "115") (name "SDRAM_CAS_O") (class "Default")
      (node (ref "JP3") (pin "7") (pinfunction "7_7") (pintype "passive"))
      (node (ref "SDRAM_1") (pin "5") (pinfunction "5_5") (pintype "passive"))
    )
    (net (code "116") (name "SDRAM_CKE_O") (class "Default")
      (node (ref "JP3") (pin "4") (pinfunction "4_4") (pintype "passive"))
      (node (ref "SDRAM_1") (pin "2") (pinfunction "2_2") (pintype "passive"))
    )
    (net (code "117") (name "SDRAM_CLK_O") (class "Default")
      (node (ref "JP3") (pin "2") (pinfunction "2_2") (pintype "passive"))
      (node (ref "SDRAM_1") (pin "1") (pinfunction "1_1") (pintype "passive"))
    )
    (net (code "118") (name "SDRAM_CS_O") (class "Default")
      (node (ref "JP3") (pin "5") (pinfunction "5_5") (pintype "passive"))
      (node (ref "SDRAM_1") (pin "3") (pinfunction "3_3") (pintype "passive"))
    )
    (net (code "119") (name "SDRAM_DATA_I[0]") (class "Default")
      (node (ref "JP4") (pin "38") (pinfunction "38_38") (pintype "passive"))
      (node (ref "SDRAM_2") (pin "25") (pinfunction "25_25") (pintype "passive"))
    )
    (net (code "120") (name "SDRAM_DATA_I[1]") (class "Default")
      (node (ref "JP4") (pin "36") (pinfunction "36_36") (pintype "passive"))
      (node (ref "SDRAM_2") (pin "24") (pinfunction "24_24") (pintype "passive"))
    )
    (net (code "121") (name "SDRAM_DATA_I[2]") (class "Default")
      (node (ref "JP4") (pin "35") (pinfunction "35_35") (pintype "passive"))
      (node (ref "SDRAM_2") (pin "23") (pinfunction "23_23") (pintype "passive"))
    )
    (net (code "122") (name "SDRAM_DATA_I[3]") (class "Default")
      (node (ref "JP4") (pin "34") (pinfunction "34_34") (pintype "passive"))
      (node (ref "SDRAM_2") (pin "22") (pinfunction "22_22") (pintype "passive"))
    )
    (net (code "123") (name "SDRAM_DATA_I[4]") (class "Default")
      (node (ref "JP4") (pin "33") (pinfunction "33_33") (pintype "passive"))
      (node (ref "SDRAM_2") (pin "21") (pinfunction "21_21") (pintype "passive"))
    )
    (net (code "124") (name "SDRAM_DATA_I[5]") (class "Default")
      (node (ref "JP4") (pin "32") (pinfunction "32_32") (pintype "passive"))
      (node (ref "SDRAM_2") (pin "20") (pinfunction "20_20") (pintype "passive"))
    )
    (net (code "125") (name "SDRAM_DATA_I[6]") (class "Default")
      (node (ref "JP4") (pin "31") (pinfunction "31_31") (pintype "passive"))
      (node (ref "SDRAM_2") (pin "19") (pinfunction "19_19") (pintype "passive"))
    )
    (net (code "126") (name "SDRAM_DATA_I[7]") (class "Default")
      (node (ref "JP4") (pin "30") (pinfunction "30_30") (pintype "passive"))
      (node (ref "SDRAM_2") (pin "18") (pinfunction "18_18") (pintype "passive"))
    )
    (net (code "127") (name "SDRAM_DATA_I[8]") (class "Default")
      (node (ref "JP4") (pin "29") (pinfunction "29_29") (pintype "passive"))
      (node (ref "SDRAM_2") (pin "17") (pinfunction "17_17") (pintype "passive"))
    )
    (net (code "128") (name "SDRAM_DATA_I[9]") (class "Default")
      (node (ref "JP4") (pin "28") (pinfunction "28_28") (pintype "passive"))
      (node (ref "SDRAM_2") (pin "16") (pinfunction "16_16") (pintype "passive"))
    )
    (net (code "129") (name "SDRAM_DATA_I[10]") (class "Default")
      (node (ref "JP4") (pin "26") (pinfunction "26_26") (pintype "passive"))
      (node (ref "SDRAM_2") (pin "15") (pinfunction "15_15") (pintype "passive"))
    )
    (net (code "130") (name "SDRAM_DATA_I[11]") (class "Default")
      (node (ref "JP4") (pin "24") (pinfunction "24_24") (pintype "passive"))
      (node (ref "SDRAM_2") (pin "14") (pinfunction "14_14") (pintype "passive"))
    )
    (net (code "131") (name "SDRAM_DATA_I[12]") (class "Default")
      (node (ref "JP4") (pin "23") (pinfunction "23_23") (pintype "passive"))
      (node (ref "SDRAM_2") (pin "13") (pinfunction "13_13") (pintype "passive"))
    )
    (net (code "132") (name "SDRAM_DATA_I[13]") (class "Default")
      (node (ref "JP4") (pin "22") (pinfunction "22_22") (pintype "passive"))
      (node (ref "SDRAM_2") (pin "12") (pinfunction "12_12") (pintype "passive"))
    )
    (net (code "133") (name "SDRAM_DATA_I[14]") (class "Default")
      (node (ref "JP4") (pin "21") (pinfunction "21_21") (pintype "passive"))
      (node (ref "SDRAM_2") (pin "11") (pinfunction "11_11") (pintype "passive"))
    )
    (net (code "134") (name "SDRAM_DATA_I[15]") (class "Default")
      (node (ref "JP4") (pin "20") (pinfunction "20_20") (pintype "passive"))
      (node (ref "SDRAM_2") (pin "10") (pinfunction "10_10") (pintype "passive"))
    )
    (net (code "135") (name "SDRAM_DATA_O[0]") (class "Default")
      (node (ref "JP4") (pin "11") (pinfunction "11_11") (pintype "passive"))
      (node (ref "SDRAM_2") (pin "9") (pinfunction "9_9") (pintype "passive"))
    )
    (net (code "136") (name "SDRAM_DATA_O[1]") (class "Default")
      (node (ref "JP4") (pin "10") (pinfunction "10_10") (pintype "passive"))
      (node (ref "SDRAM_2") (pin "8") (pinfunction "8_8") (pintype "passive"))
    )
    (net (code "137") (name "SDRAM_DATA_O[2]") (class "Default")
      (node (ref "JP4") (pin "9") (pinfunction "9_9") (pintype "passive"))
      (node (ref "SDRAM_2") (pin "7") (pinfunction "7_7") (pintype "passive"))
    )
    (net (code "138") (name "SDRAM_DATA_O[3]") (class "Default")
      (node (ref "JP4") (pin "8") (pinfunction "8_8") (pintype "passive"))
      (node (ref "SDRAM_2") (pin "6") (pinfunction "6_6") (pintype "passive"))
    )
    (net (code "139") (name "SDRAM_DATA_O[4]") (class "Default")
      (node (ref "JP4") (pin "7") (pinfunction "7_7") (pintype "passive"))
      (node (ref "SDRAM_2") (pin "5") (pinfunction "5_5") (pintype "passive"))
    )
    (net (code "140") (name "SDRAM_DATA_O[5]") (class "Default")
      (node (ref "JP4") (pin "6") (pinfunction "6_6") (pintype "passive"))
      (node (ref "SDRAM_2") (pin "4") (pinfunction "4_4") (pintype "passive"))
    )
    (net (code "141") (name "SDRAM_DATA_O[6]") (class "Default")
      (node (ref "JP4") (pin "5") (pinfunction "5_5") (pintype "passive"))
      (node (ref "SDRAM_2") (pin "3") (pinfunction "3_3") (pintype "passive"))
    )
    (net (code "142") (name "SDRAM_DATA_O[7]") (class "Default")
      (node (ref "JP4") (pin "4") (pinfunction "4_4") (pintype "passive"))
      (node (ref "SDRAM_2") (pin "2") (pinfunction "2_2") (pintype "passive"))
    )
    (net (code "143") (name "SDRAM_DATA_O[8]") (class "Default")
      (node (ref "JP4") (pin "2") (pinfunction "2_2") (pintype "passive"))
      (node (ref "SDRAM_2") (pin "1") (pinfunction "1_1") (pintype "passive"))
    )
    (net (code "144") (name "SDRAM_DATA_O[9]") (class "Default")
      (node (ref "JP3") (pin "40") (pinfunction "40_40") (pintype "passive"))
      (node (ref "SDRAM_1") (pin "32") (pinfunction "32_32") (pintype "passive"))
    )
    (net (code "145") (name "SDRAM_DATA_O[10]") (class "Default")
      (node (ref "JP3") (pin "38") (pinfunction "38_38") (pintype "passive"))
      (node (ref "SDRAM_1") (pin "31") (pinfunction "31_31") (pintype "passive"))
    )
    (net (code "146") (name "SDRAM_DATA_O[11]") (class "Default")
      (node (ref "JP3") (pin "36") (pinfunction "36_36") (pintype "passive"))
      (node (ref "SDRAM_1") (pin "30") (pinfunction "30_30") (pintype "passive"))
    )
    (net (code "147") (name "SDRAM_DATA_O[12]") (class "Default")
      (node (ref "JP3") (pin "35") (pinfunction "35_35") (pintype "passive"))
      (node (ref "SDRAM_1") (pin "29") (pinfunction "29_29") (pintype "passive"))
    )
    (net (code "148") (name "SDRAM_DATA_O[13]") (class "Default")
      (node (ref "JP3") (pin "34") (pinfunction "34_34") (pintype "passive"))
      (node (ref "SDRAM_1") (pin "28") (pinfunction "28_28") (pintype "passive"))
    )
    (net (code "149") (name "SDRAM_DATA_O[14]") (class "Default")
      (node (ref "JP3") (pin "33") (pinfunction "33_33") (pintype "passive"))
      (node (ref "SDRAM_1") (pin "27") (pinfunction "27_27") (pintype "passive"))
    )
    (net (code "150") (name "SDRAM_DATA_O[15]") (class "Default")
      (node (ref "JP3") (pin "32") (pinfunction "32_32") (pintype "passive"))
      (node (ref "SDRAM_1") (pin "26") (pinfunction "26_26") (pintype "passive"))
    )
    (net (code "151") (name "SDRAM_DQM_O[0]") (class "Default")
      (node (ref "JP3") (pin "12") (pinfunction "12_12") (pintype "passive"))
      (node (ref "SDRAM_1") (pin "10") (pinfunction "10_10") (pintype "passive"))
    )
    (net (code "152") (name "SDRAM_DQM_O[1]") (class "Default")
      (node (ref "JP3") (pin "11") (pinfunction "11_11") (pintype "passive"))
      (node (ref "SDRAM_1") (pin "9") (pinfunction "9_9") (pintype "passive"))
    )
    (net (code "153") (name "SDRAM_DQM_O[2]") (class "Default")
      (node (ref "JP3") (pin "10") (pinfunction "10_10") (pintype "passive"))
      (node (ref "SDRAM_1") (pin "8") (pinfunction "8_8") (pintype "passive"))
    )
    (net (code "154") (name "SDRAM_DQM_O[3]") (class "Default")
      (node (ref "JP3") (pin "9") (pinfunction "9_9") (pintype "passive"))
      (node (ref "SDRAM_1") (pin "7") (pinfunction "7_7") (pintype "passive"))
    )
    (net (code "155") (name "SDRAM_DRIVE_O") (class "Default")
      (node (ref "JP4") (pin "40") (pinfunction "40_40") (pintype "passive"))
      (node (ref "SDRAM_2") (pin "26") (pinfunction "26_26") (pintype "passive"))
    )
    (net (code "156") (name "SDRAM_RAS_O") (class "Default")
      (node (ref "JP3") (pin "6") (pinfunction "6_6") (pintype "passive"))
      (node (ref "SDRAM_1") (pin "4") (pinfunction "4_4") (pintype "passive"))
    )
    (net (code "157") (name "SDRAM_WE_O") (class "Default")
      (node (ref "JP3") (pin "8") (pinfunction "8_8") (pintype "passive"))
      (node (ref "SDRAM_1") (pin "6") (pinfunction "6_6") (pintype "passive"))
    )
    (net (code "158") (name "SD_QSPI_CS") (class "Default")
      (node (ref "JP1") (pin "23") (pinfunction "23_23") (pintype "passive"))
      (node (ref "SD") (pin "7") (pinfunction "7_7") (pintype "passive"))
    )
    (net (code "159") (name "SD_QSPI_MISO") (class "Default")
      (node (ref "JP1") (pin "26") (pinfunction "26_26") (pintype "passive"))
      (node (ref "SD") (pin "3") (pinfunction "3_3") (pintype "passive"))
    )
    (net (code "160") (name "SD_QSPI_MOSI") (class "Default")
      (node (ref "JP1") (pin "28") (pinfunction "28_28") (pintype "passive"))
      (node (ref "SD") (pin "1") (pinfunction "1_1") (pintype "passive"))
    )
    (net (code "161") (name "SD_QSPI_SCK") (class "Default")
      (node (ref "JP1") (pin "24") (pinfunction "24_24") (pintype "passive"))
      (node (ref "SD") (pin "5") (pinfunction "5_5") (pintype "passive"))
    )
    (net (code "162") (name "SYS_CLK") (class "Default")
      (node (ref "J4") (pin "5") (pinfunction "5_5") (pintype "bidirectional"))
      (node (ref "JP4") (pin "14") (pinfunction "14_14") (pintype "passive"))
      (node (ref "SYS_CLK") (pin "2") (pinfunction "2_2") (pintype "passive"))
    )
    (net (code "163") (name "TCK") (class "Default")
      (node (ref "IC1") (pin "14") (pinfunction "B6_14") (pintype "bidirectional"))
      (node (ref "JTAG_20_PIN") (pin "9") (pinfunction "9_9") (pintype "passive"))
    )
    (net (code "164") (name "TDI") (class "Default")
      (node (ref "IC1") (pin "12") (pinfunction "B8_12") (pintype "bidirectional"))
      (node (ref "JTAG_20_PIN") (pin "5") (pinfunction "5_5") (pintype "passive"))
    )
    (net (code "165") (name "TDO") (class "Default")
      (node (ref "IC1") (pin "13") (pinfunction "B7_13") (pintype "bidirectional"))
      (node (ref "JTAG_20_PIN") (pin "13") (pinfunction "13_13") (pintype "passive"))
    )
    (net (code "166") (name "TMS") (class "Default")
      (node (ref "IC1") (pin "15") (pinfunction "B5_15") (pintype "bidirectional"))
      (node (ref "JTAG_20_PIN") (pin "7") (pinfunction "7_7") (pintype "passive"))
    )
    (net (code "167") (name "TX") (class "Default")
      (node (ref "IC2") (pin "17") (pinfunction "B3_17") (pintype "bidirectional"))
      (node (ref "USB-UART_1") (pin "4") (pinfunction "4_4") (pintype "passive"))
    )
    (net (code "168") (name "UART_RXD") (class "Default")
      (node (ref "JP1") (pin "30") (pinfunction "30_30") (pintype "passive"))
      (node (ref "UART") (pin "1") (pinfunction "1_1") (pintype "passive"))
    )
    (net (code "169") (name "UART_TXD") (class "Default")
      (node (ref "JP1") (pin "29") (pinfunction "29_29") (pintype "passive"))
      (node (ref "UART") (pin "3") (pinfunction "3_3") (pintype "passive"))
    )
    (net (code "170") (name "VDD") (class "Default")
      (node (ref "C12") (pin "1") (pinfunction "1_1") (pintype "passive"))
      (node (ref "C13") (pin "1") (pinfunction "1_1") (pintype "passive"))
      (node (ref "JP1") (pin "13") (pinfunction "13_13") (pintype "passive"))
      (node (ref "JP1") (pin "39") (pinfunction "39_39") (pintype "passive"))
      (node (ref "JP2") (pin "13") (pinfunction "13_13") (pintype "passive"))
      (node (ref "JP2") (pin "39") (pinfunction "39_39") (pintype "passive"))
      (node (ref "JP3") (pin "15") (pinfunction "15_15") (pintype "passive"))
      (node (ref "JP3") (pin "39") (pinfunction "39_39") (pintype "passive"))
      (node (ref "JP4") (pin "13") (pinfunction "13_13") (pintype "passive"))
      (node (ref "JP4") (pin "39") (pinfunction "39_39") (pintype "passive"))
      (node (ref "POWER") (pin "2") (pinfunction "2_2") (pintype "passive"))
      (node (ref "POWER_LED") (pin "1") (pinfunction "1_1") (pintype "passive"))
    )
    (net (code "171") (name "VDDO") (class "Default")
      (node (ref "C1") (pin "1") (pinfunction "1_1") (pintype "passive"))
      (node (ref "C11") (pin "1") (pinfunction "1_1") (pintype "passive"))
      (node (ref "C14") (pin "1") (pinfunction "1_1") (pintype "passive"))
      (node (ref "C3") (pin "1") (pinfunction "1_1") (pintype "passive"))
      (node (ref "IC1") (pin "10") (pinfunction "OE_10") (pintype "bidirectional"))
      (node (ref "IC1") (pin "2") (pinfunction "VCCA_2") (pintype "bidirectional"))
      (node (ref "IC2") (pin "10") (pinfunction "OE_10") (pintype "bidirectional"))
      (node (ref "IC2") (pin "2") (pinfunction "VCCA_2") (pintype "bidirectional"))
      (node (ref "JP1") (pin "1") (pinfunction "1_1") (pintype "passive"))
      (node (ref "JP1") (pin "27") (pinfunction "27_27") (pintype "passive"))
      (node (ref "JP2") (pin "1") (pinfunction "1_1") (pintype "passive"))
      (node (ref "JP2") (pin "25") (pinfunction "25_25") (pintype "passive"))
      (node (ref "JP3") (pin "1") (pinfunction "1_1") (pintype "passive"))
      (node (ref "JP3") (pin "25") (pinfunction "25_25") (pintype "passive"))
      (node (ref "JP4") (pin "1") (pinfunction "1_1") (pintype "passive"))
      (node (ref "JP4") (pin "27") (pinfunction "27_27") (pintype "passive"))
      (node (ref "POWER") (pin "4") (pinfunction "4_4") (pintype "passive"))
      (node (ref "POWER_LED") (pin "3") (pinfunction "3_3") (pintype "passive"))
    )
    (net (code "172") (name "VDDO_LED") (class "Default")
      (node (ref "POWER_LED") (pin "4") (pinfunction "4_4") (pintype "passive"))
      (node (ref "Q6") (pin "1") (pinfunction "G_1") (pintype "bidirectional"))
      (node (ref "R12") (pin "2") (pinfunction "2_2") (pintype "passive"))
    )
    (net (code "173") (name "VDD_1.8_1") (class "Default")
      (node (ref "C10") (pin "1") (pinfunction "1_1") (pintype "passive"))
      (node (ref "IC5") (pin "2") (pinfunction "VOUT_1_2") (pintype "bidirectional"))
      (node (ref "IC5") (pin "4") (pinfunction "VOUT_2_4") (pintype "bidirectional"))
      (node (ref "POWER") (pin "1") (pinfunction "1_1") (pintype "passive"))
    )
    (net (code "174") (name "VDD_1.8_2") (class "Default")
      (node (ref "C6") (pin "1") (pinfunction "1_1") (pintype "passive"))
      (node (ref "IC3") (pin "2") (pinfunction "VOUT_1_2") (pintype "bidirectional"))
      (node (ref "IC3") (pin "4") (pinfunction "VOUT_2_4") (pintype "bidirectional"))
      (node (ref "POWER") (pin "3") (pinfunction "3_3") (pintype "passive"))
    )
    (net (code "175") (name "VDD_3V3") (class "Default")
      (node (ref "3.3V_GPIO") (pin "1") (pinfunction "1_1") (pintype "passive"))
      (node (ref "C2") (pin "1") (pinfunction "1_1") (pintype "passive"))
      (node (ref "C4") (pin "1") (pinfunction "1_1") (pintype "passive"))
      (node (ref "C5") (pin "1") (pinfunction "1_1") (pintype "passive"))
      (node (ref "C9") (pin "1") (pinfunction "1_1") (pintype "passive"))
      (node (ref "FLASH") (pin "1") (pinfunction "1_1") (pintype "passive"))
      (node (ref "FLASH") (pin "2") (pinfunction "2_2") (pintype "passive"))
      (node (ref "IC1") (pin "19") (pinfunction "VCCB_19") (pintype "bidirectional"))
      (node (ref "IC2") (pin "19") (pinfunction "VCCB_19") (pintype "bidirectional"))
      (node (ref "IC3") (pin "3") (pinfunction "VIN_3") (pintype "bidirectional"))
      (node (ref "IC5") (pin "3") (pinfunction "VIN_3") (pintype "bidirectional"))
      (node (ref "JTAG_20_PIN") (pin "1") (pinfunction "1_1") (pintype "passive"))
      (node (ref "JTAG_20_PIN") (pin "2") (pinfunction "2_2") (pintype "passive"))
      (node (ref "Q5") (pin "1") (pinfunction "G_1") (pintype "bidirectional"))
      (node (ref "R11") (pin "2") (pinfunction "2_2") (pintype "passive"))
      (node (ref "R13") (pin "2") (pinfunction "2_2") (pintype "passive"))
      (node (ref "R15") (pin "2") (pinfunction "2_2") (pintype "passive"))
      (node (ref "R16") (pin "2") (pinfunction "2_2") (pintype "passive"))
      (node (ref "R17") (pin "2") (pinfunction "2_2") (pintype "passive"))
      (node (ref "SD_CARD") (pin "1") (pinfunction "1_1") (pintype "passive"))
      (node (ref "SD_CARD") (pin "2") (pinfunction "2_2") (pintype "passive"))
      (node (ref "USB-UART_1") (pin "3") (pinfunction "3_3") (pintype "passive"))
    )
    (net (code "176") (name "VDD_3V3_GPIO") (class "Default")
      (node (ref "3.3V_GPIO") (pin "2") (pinfunction "2_2") (pintype "passive"))
      (node (ref "GPIO_1") (pin "29") (pinfunction "29_29") (pintype "passive"))
      (node (ref "GPIO_2") (pin "29") (pinfunction "29_29") (pintype "passive"))
    )
    (net (code "177") (name "VDD_5V_USB") (class "Default")
      (node (ref "USB-UART_2") (pin "2") (pinfunction "2_2") (pintype "passive"))
    )
    (net (code "178") (name "VDD_LED") (class "Default")
      (node (ref "POWER_LED") (pin "2") (pinfunction "2_2") (pintype "passive"))
      (node (ref "Q8") (pin "1") (pinfunction "G_1") (pintype "bidirectional"))
      (node (ref "R10") (pin "2") (pinfunction "2_2") (pintype "passive"))
    )
    (net (code "179") (name "unconnected-(FLASH-Pad5)") (class "Default")
      (node (ref "FLASH") (pin "5") (pinfunction "5_5") (pintype "passive"))
    )
    (net (code "180") (name "unconnected-(FLASH-Pad7)") (class "Default")
      (node (ref "FLASH") (pin "7") (pinfunction "7_7") (pintype "passive"))
    )
    (net (code "181") (name "unconnected-(FLASH-Pad9)") (class "Default")
      (node (ref "FLASH") (pin "9") (pinfunction "9_9") (pintype "passive"))
    )
    (net (code "182") (name "unconnected-(FLASH-Pad11)") (class "Default")
      (node (ref "FLASH") (pin "11") (pinfunction "11_11") (pintype "passive"))
    )
    (net (code "183") (name "unconnected-(GPIO_1-Pad1)") (class "Default")
      (node (ref "GPIO_1") (pin "1") (pinfunction "1_1") (pintype "passive"))
    )
    (net (code "184") (name "unconnected-(GPIO_1-Pad3)") (class "Default")
      (node (ref "GPIO_1") (pin "3") (pinfunction "3_3") (pintype "passive"))
    )
    (net (code "185") (name "unconnected-(GPIO_1-Pad11)") (class "Default")
      (node (ref "GPIO_1") (pin "11") (pinfunction "11_11") (pintype "passive"))
    )
    (net (code "186") (name "unconnected-(GPIO_2-Pad1)") (class "Default")
      (node (ref "GPIO_2") (pin "1") (pinfunction "1_1") (pintype "passive"))
    )
    (net (code "187") (name "unconnected-(GPIO_2-Pad3)") (class "Default")
      (node (ref "GPIO_2") (pin "3") (pinfunction "3_3") (pintype "passive"))
    )
    (net (code "188") (name "unconnected-(GPIO_2-Pad9)") (class "Default")
      (node (ref "GPIO_2") (pin "9") (pinfunction "9_9") (pintype "passive"))
    )
    (net (code "189") (name "unconnected-(GPIO_2-Pad10)") (class "Default")
      (node (ref "GPIO_2") (pin "10") (pinfunction "10_10") (pintype "passive"))
    )
    (net (code "190") (name "unconnected-(GPIO_2-Pad11)") (class "Default")
      (node (ref "GPIO_2") (pin "11") (pinfunction "11_11") (pintype "passive"))
    )
    (net (code "191") (name "unconnected-(GPIO_2-Pad13)") (class "Default")
      (node (ref "GPIO_2") (pin "13") (pinfunction "13_13") (pintype "passive"))
    )
    (net (code "192") (name "unconnected-(GPIO_2-Pad14)") (class "Default")
      (node (ref "GPIO_2") (pin "14") (pinfunction "14_14") (pintype "passive"))
    )
    (net (code "193") (name "unconnected-(GPIO_2-Pad15)") (class "Default")
      (node (ref "GPIO_2") (pin "15") (pinfunction "15_15") (pintype "passive"))
    )
    (net (code "194") (name "unconnected-(GPIO_2-Pad16)") (class "Default")
      (node (ref "GPIO_2") (pin "16") (pinfunction "16_16") (pintype "passive"))
    )
    (net (code "195") (name "unconnected-(GPIO_2-Pad17)") (class "Default")
      (node (ref "GPIO_2") (pin "17") (pinfunction "17_17") (pintype "passive"))
    )
    (net (code "196") (name "unconnected-(GPIO_2-Pad18)") (class "Default")
      (node (ref "GPIO_2") (pin "18") (pinfunction "18_18") (pintype "passive"))
    )
    (net (code "197") (name "unconnected-(GPIO_2-Pad19)") (class "Default")
      (node (ref "GPIO_2") (pin "19") (pinfunction "19_19") (pintype "passive"))
    )
    (net (code "198") (name "unconnected-(GPIO_2-Pad20)") (class "Default")
      (node (ref "GPIO_2") (pin "20") (pinfunction "20_20") (pintype "passive"))
    )
    (net (code "199") (name "unconnected-(GPIO_2-Pad21)") (class "Default")
      (node (ref "GPIO_2") (pin "21") (pinfunction "21_21") (pintype "passive"))
    )
    (net (code "200") (name "unconnected-(GPIO_2-Pad22)") (class "Default")
      (node (ref "GPIO_2") (pin "22") (pinfunction "22_22") (pintype "passive"))
    )
    (net (code "201") (name "unconnected-(GPIO_2-Pad23)") (class "Default")
      (node (ref "GPIO_2") (pin "23") (pinfunction "23_23") (pintype "passive"))
    )
    (net (code "202") (name "unconnected-(GPIO_2-Pad24)") (class "Default")
      (node (ref "GPIO_2") (pin "24") (pinfunction "24_24") (pintype "passive"))
    )
    (net (code "203") (name "unconnected-(GPIO_2-Pad25)") (class "Default")
      (node (ref "GPIO_2") (pin "25") (pinfunction "25_25") (pintype "passive"))
    )
    (net (code "204") (name "unconnected-(GPIO_2-Pad26)") (class "Default")
      (node (ref "GPIO_2") (pin "26") (pinfunction "26_26") (pintype "passive"))
    )
    (net (code "205") (name "unconnected-(GPIO_2-Pad27)") (class "Default")
      (node (ref "GPIO_2") (pin "27") (pinfunction "27_27") (pintype "passive"))
    )
    (net (code "206") (name "unconnected-(GPIO_2-Pad28)") (class "Default")
      (node (ref "GPIO_2") (pin "28") (pinfunction "28_28") (pintype "passive"))
    )
    (net (code "207") (name "unconnected-(GPIO_2-Pad31)") (class "Default")
      (node (ref "GPIO_2") (pin "31") (pinfunction "31_31") (pintype "passive"))
    )
    (net (code "208") (name "unconnected-(GPIO_2-Pad32)") (class "Default")
      (node (ref "GPIO_2") (pin "32") (pinfunction "32_32") (pintype "passive"))
    )
    (net (code "209") (name "unconnected-(GPIO_2-Pad33)") (class "Default")
      (node (ref "GPIO_2") (pin "33") (pinfunction "33_33") (pintype "passive"))
    )
    (net (code "210") (name "unconnected-(GPIO_2-Pad34)") (class "Default")
      (node (ref "GPIO_2") (pin "34") (pinfunction "34_34") (pintype "passive"))
    )
    (net (code "211") (name "unconnected-(IC2-A1-Pad1)") (class "Default")
      (node (ref "IC2") (pin "1") (pinfunction "A1_1") (pintype "bidirectional"))
    )
    (net (code "212") (name "unconnected-(IC2-A8-Pad9)") (class "Default")
      (node (ref "IC2") (pin "9") (pinfunction "A8_9") (pintype "bidirectional"))
    )
    (net (code "213") (name "unconnected-(IC2-B1-Pad20)") (class "Default")
      (node (ref "IC2") (pin "20") (pinfunction "B1_20") (pintype "bidirectional"))
    )
    (net (code "214") (name "unconnected-(IC2-B8-Pad12)") (class "Default")
      (node (ref "IC2") (pin "12") (pinfunction "B8_12") (pintype "bidirectional"))
    )
    (net (code "215") (name "unconnected-(JTAG_20_PIN-Pad3)") (class "Default")
      (node (ref "JTAG_20_PIN") (pin "3") (pinfunction "3_3") (pintype "passive"))
    )
    (net (code "216") (name "unconnected-(JTAG_20_PIN-Pad11)") (class "Default")
      (node (ref "JTAG_20_PIN") (pin "11") (pinfunction "11_11") (pintype "passive"))
    )
    (net (code "217") (name "unconnected-(JTAG_20_PIN-Pad15)") (class "Default")
      (node (ref "JTAG_20_PIN") (pin "15") (pinfunction "15_15") (pintype "passive"))
    )
    (net (code "218") (name "unconnected-(JTAG_20_PIN-Pad17)") (class "Default")
      (node (ref "JTAG_20_PIN") (pin "17") (pinfunction "17_17") (pintype "passive"))
    )
    (net (code "219") (name "unconnected-(JTAG_20_PIN-Pad19)") (class "Default")
      (node (ref "JTAG_20_PIN") (pin "19") (pinfunction "19_19") (pintype "passive"))
    )
    (net (code "220") (name "unconnected-(SD_CARD-Pad5)") (class "Default")
      (node (ref "SD_CARD") (pin "5") (pinfunction "5_5") (pintype "passive"))
    )
    (net (code "221") (name "unconnected-(SD_CARD-Pad7)") (class "Default")
      (node (ref "SD_CARD") (pin "7") (pinfunction "7_7") (pintype "passive"))
    )
    (net (code "222") (name "unconnected-(SD_CARD-Pad9)") (class "Default")
      (node (ref "SD_CARD") (pin "9") (pinfunction "9_9") (pintype "passive"))
    )
    (net (code "223") (name "unconnected-(SD_CARD-Pad11)") (class "Default")
      (node (ref "SD_CARD") (pin "11") (pinfunction "11_11") (pintype "passive"))
    )
    (net (code "224") (name "unconnected-(USB-UART_2-Pad1)") (class "Default")
      (node (ref "USB-UART_2") (pin "1") (pinfunction "1_1") (pintype "passive"))
    )
    (net (code "225") (name "unconnected-(USB-UART_2-Pad3)") (class "Default")
      (node (ref "USB-UART_2") (pin "3") (pinfunction "3_3") (pintype "passive"))
    )
    (net (code "226") (name "unconnected-(USB-UART_2-Pad4)") (class "Default")
      (node (ref "USB-UART_2") (pin "4") (pinfunction "4_4") (pintype "passive"))
    )
  )
)
